# cnd_distributor.net
KiCad netlist of a schematic drawn in EAGLE
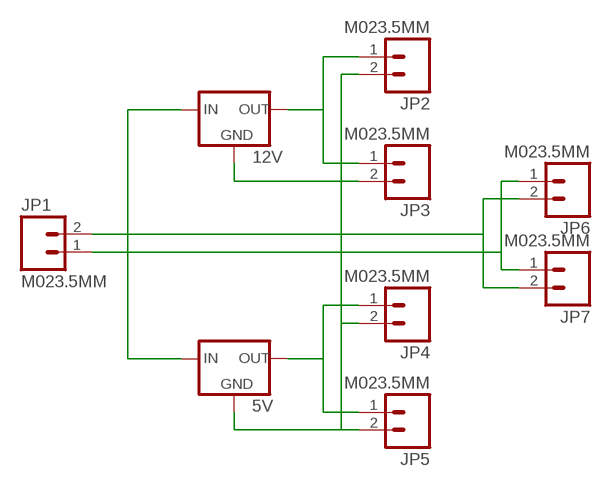
[diagram p0: schematic, sheet 1]

(export (version "E")
  (design (tool "Eeschema 10.0.6"))
  (components
    (comp (ref "5V")
      (value "78XXS")
      (footprint "eagle-import:78XXS")
      (libsource (lib "eagle-import") (part "78XXS"))
    )
    (comp (ref "12V")
      (value "78XXS")
      (footprint "eagle-import:78XXS")
      (libsource (lib "eagle-import") (part "78XXS"))
    )
    (comp (ref "JP1")
      (value "M023.5MM")
      (footprint "eagle-import:SCREWTERMINAL-3.5MM-2")
      (libsource (lib "eagle-import") (part "M023.5MM"))
    )
    (comp (ref "JP2")
      (value "M023.5MM")
      (footprint "eagle-import:SCREWTERMINAL-3.5MM-2")
      (libsource (lib "eagle-import") (part "M023.5MM"))
    )
    (comp (ref "JP3")
      (value "M023.5MM")
      (footprint "eagle-import:SCREWTERMINAL-3.5MM-2")
      (libsource (lib "eagle-import") (part "M023.5MM"))
    )
    (comp (ref "JP4")
      (value "M023.5MM")
      (footprint "eagle-import:SCREWTERMINAL-3.5MM-2")
      (libsource (lib "eagle-import") (part "M023.5MM"))
    )
    (comp (ref "JP5")
      (value "M023.5MM")
      (footprint "eagle-import:SCREWTERMINAL-3.5MM-2")
      (libsource (lib "eagle-import") (part "M023.5MM"))
    )
    (comp (ref "JP6")
      (value "M023.5MM")
      (footprint "eagle-import:SCREWTERMINAL-3.5MM-2")
      (libsource (lib "eagle-import") (part "M023.5MM"))
    )
    (comp (ref "JP7")
      (value "M023.5MM")
      (footprint "eagle-import:SCREWTERMINAL-3.5MM-2")
      (libsource (lib "eagle-import") (part "M023.5MM"))
    )
  )
  (nets
    (net (code "1") (name "Net-(5V-PadOUT)") (class "Default")
      (node (ref "5V") (pin "OUT") (pinfunction "OUT_OUT") (pintype "passive"))
      (node (ref "JP4") (pin "1") (pinfunction "1_1") (pintype "passive"))
      (node (ref "JP5") (pin "1") (pinfunction "1_1") (pintype "passive"))
    )
    (net (code "2") (name "Net-(12V-PadGND)") (class "Default")
      (node (ref "12V") (pin "GND") (pinfunction "GND_GND") (pintype "input"))
      (node (ref "5V") (pin "GND") (pinfunction "GND_GND") (pintype "input"))
      (node (ref "JP1") (pin "2") (pinfunction "2_2") (pintype "passive"))
      (node (ref "JP2") (pin "2") (pinfunction "2_2") (pintype "passive"))
      (node (ref "JP3") (pin "2") (pinfunction "2_2") (pintype "passive"))
      (node (ref "JP4") (pin "2") (pinfunction "2_2") (pintype "passive"))
      (node (ref "JP5") (pin "2") (pinfunction "2_2") (pintype "passive"))
      (node (ref "JP6") (pin "2") (pinfunction "2_2") (pintype "passive"))
      (node (ref "JP7") (pin "2") (pinfunction "2_2") (pintype "passive"))
    )
    (net (code "3") (name "Net-(12V-PadIN)") (class "Default")
      (node (ref "12V") (pin "IN") (pinfunction "IN_IN") (pintype "input"))
      (node (ref "5V") (pin "IN") (pinfunction "IN_IN") (pintype "input"))
      (node (ref "JP1") (pin "1") (pinfunction "1_1") (pintype "passive"))
      (node (ref "JP6") (pin "1") (pinfunction "1_1") (pintype "passive"))
      (node (ref "JP7") (pin "1") (pinfunction "1_1") (pintype "passive"))
    )
    (net (code "4") (name "Net-(12V-PadOUT)") (class "Default")
      (node (ref "12V") (pin "OUT") (pinfunction "OUT_OUT") (pintype "passive"))
      (node (ref "JP2") (pin "1") (pinfunction "1_1") (pintype "passive"))
      (node (ref "JP3") (pin "1") (pinfunction "1_1") (pintype "passive"))
    )
  )
)
